# Power_Supply.net
KiCad netlist of a schematic drawn in Altium Designer
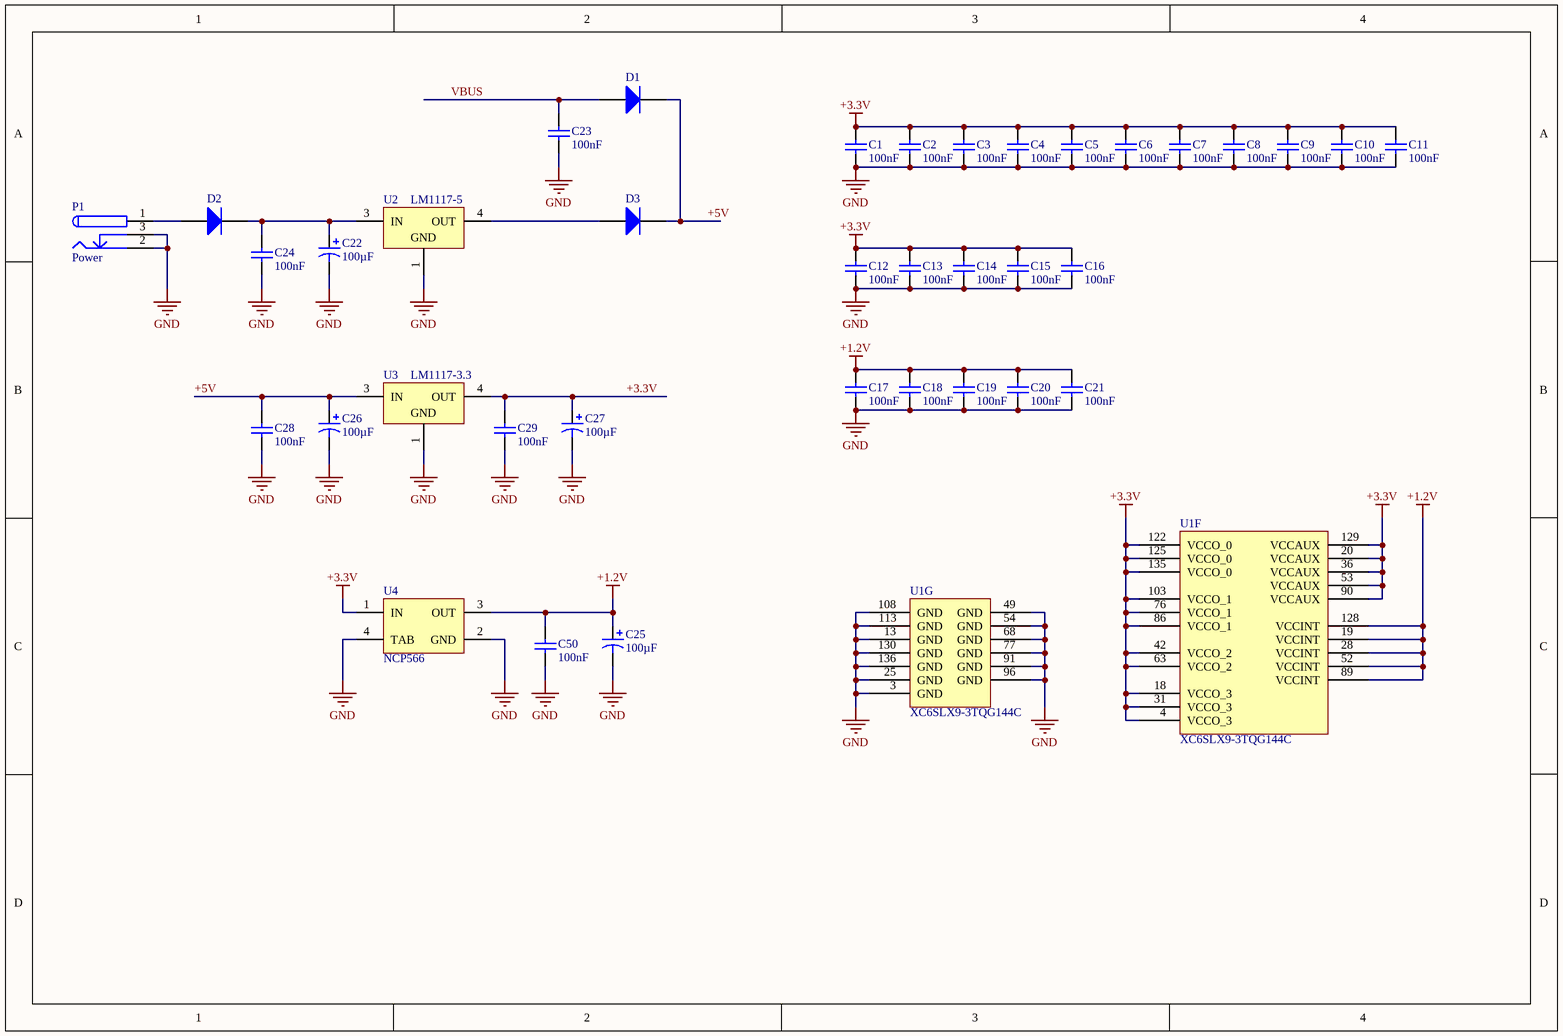
[diagram p0: Power Supply.SchDoc]

(export (version "E")
  (design (tool "Eeschema 10.0.6"))
  (components
    (comp (ref "C1")
      (value "100nF")
      (footprint "6-0805_n")
      (description "Capacitor")
      (fields (field (name "Comment") "Cap") (field (name "PUBLISHER") "Altium Limited"))
      (libsource (lib "Miscellaneous Devices") (part "Cap"))
    )
    (comp (ref "C2")
      (value "100nF")
      (footprint "6-0805_n")
      (description "Capacitor")
      (fields (field (name "Comment") "Cap") (field (name "PUBLISHER") "Altium Limited"))
      (libsource (lib "Miscellaneous Devices") (part "Cap"))
    )
    (comp (ref "C3")
      (value "100nF")
      (footprint "6-0805_n")
      (description "Capacitor")
      (fields (field (name "Comment") "Cap") (field (name "PUBLISHER") "Altium Limited"))
      (libsource (lib "Miscellaneous Devices") (part "Cap"))
    )
    (comp (ref "C4")
      (value "100nF")
      (footprint "6-0805_n")
      (description "Capacitor")
      (fields (field (name "Comment") "Cap") (field (name "PUBLISHER") "Altium Limited"))
      (libsource (lib "Miscellaneous Devices") (part "Cap"))
    )
    (comp (ref "C5")
      (value "100nF")
      (footprint "6-0805_n")
      (description "Capacitor")
      (fields (field (name "Comment") "Cap") (field (name "PUBLISHER") "Altium Limited"))
      (libsource (lib "Miscellaneous Devices") (part "Cap"))
    )
    (comp (ref "C6")
      (value "100nF")
      (footprint "6-0805_n")
      (description "Capacitor")
      (fields (field (name "Comment") "Cap") (field (name "PUBLISHER") "Altium Limited"))
      (libsource (lib "Miscellaneous Devices") (part "Cap"))
    )
    (comp (ref "C7")
      (value "100nF")
      (footprint "6-0805_n")
      (description "Capacitor")
      (fields (field (name "Comment") "Cap") (field (name "PUBLISHER") "Altium Limited"))
      (libsource (lib "Miscellaneous Devices") (part "Cap"))
    )
    (comp (ref "C8")
      (value "100nF")
      (footprint "6-0805_n")
      (description "Capacitor")
      (fields (field (name "Comment") "Cap") (field (name "PUBLISHER") "Altium Limited"))
      (libsource (lib "Miscellaneous Devices") (part "Cap"))
    )
    (comp (ref "C9")
      (value "100nF")
      (footprint "6-0805_n")
      (description "Capacitor")
      (fields (field (name "Comment") "Cap") (field (name "PUBLISHER") "Altium Limited"))
      (libsource (lib "Miscellaneous Devices") (part "Cap"))
    )
    (comp (ref "C10")
      (value "100nF")
      (footprint "6-0805_n")
      (description "Capacitor")
      (fields (field (name "Comment") "Cap") (field (name "PUBLISHER") "Altium Limited"))
      (libsource (lib "Miscellaneous Devices") (part "Cap"))
    )
    (comp (ref "C11")
      (value "100nF")
      (footprint "6-0805_n")
      (description "Capacitor")
      (fields (field (name "Comment") "Cap") (field (name "PUBLISHER") "Altium Limited"))
      (libsource (lib "Miscellaneous Devices") (part "Cap"))
    )
    (comp (ref "C12")
      (value "100nF")
      (footprint "6-0805_n")
      (description "Capacitor")
      (fields (field (name "Comment") "Cap") (field (name "PUBLISHER") "Altium Limited"))
      (libsource (lib "Miscellaneous Devices") (part "Cap"))
    )
    (comp (ref "C13")
      (value "100nF")
      (footprint "6-0805_n")
      (description "Capacitor")
      (fields (field (name "Comment") "Cap") (field (name "PUBLISHER") "Altium Limited"))
      (libsource (lib "Miscellaneous Devices") (part "Cap"))
    )
    (comp (ref "C14")
      (value "100nF")
      (footprint "6-0805_n")
      (description "Capacitor")
      (fields (field (name "Comment") "Cap") (field (name "PUBLISHER") "Altium Limited"))
      (libsource (lib "Miscellaneous Devices") (part "Cap"))
    )
    (comp (ref "C15")
      (value "100nF")
      (footprint "6-0805_n")
      (description "Capacitor")
      (fields (field (name "Comment") "Cap") (field (name "PUBLISHER") "Altium Limited"))
      (libsource (lib "Miscellaneous Devices") (part "Cap"))
    )
    (comp (ref "C16")
      (value "100nF")
      (footprint "6-0805_n")
      (description "Capacitor")
      (fields (field (name "Comment") "Cap") (field (name "PUBLISHER") "Altium Limited"))
      (libsource (lib "Miscellaneous Devices") (part "Cap"))
    )
    (comp (ref "C17")
      (value "100nF")
      (footprint "6-0805_n")
      (description "Capacitor")
      (fields (field (name "Comment") "Cap") (field (name "PUBLISHER") "Altium Limited"))
      (libsource (lib "Miscellaneous Devices") (part "Cap"))
    )
    (comp (ref "C18")
      (value "100nF")
      (footprint "6-0805_n")
      (description "Capacitor")
      (fields (field (name "Comment") "Cap") (field (name "PUBLISHER") "Altium Limited"))
      (libsource (lib "Miscellaneous Devices") (part "Cap"))
    )
    (comp (ref "C19")
      (value "100nF")
      (footprint "6-0805_n")
      (description "Capacitor")
      (fields (field (name "Comment") "Cap") (field (name "PUBLISHER") "Altium Limited"))
      (libsource (lib "Miscellaneous Devices") (part "Cap"))
    )
    (comp (ref "C20")
      (value "100nF")
      (footprint "6-0805_n")
      (description "Capacitor")
      (fields (field (name "Comment") "Cap") (field (name "PUBLISHER") "Altium Limited"))
      (libsource (lib "Miscellaneous Devices") (part "Cap"))
    )
    (comp (ref "C21")
      (value "100nF")
      (footprint "6-0805_n")
      (description "Capacitor")
      (fields (field (name "Comment") "Cap") (field (name "PUBLISHER") "Altium Limited"))
      (libsource (lib "Miscellaneous Devices") (part "Cap"))
    )
    (comp (ref "C22")
      (value "100µF")
      (footprint "ECAP 6.3mm")
      (description "Polarized Capacitor (Surface Mount)")
      (fields (field (name "Comment") "Cap Pol3") (field (name "PUBLISHER") "Altium Limited"))
      (libsource (lib "Miscellaneous Devices") (part "Cap Pol3"))
    )
    (comp (ref "C23")
      (value "100nF")
      (footprint "6-0805_n")
      (description "Capacitor")
      (fields (field (name "Comment") "Cap") (field (name "PUBLISHER") "Altium Limited"))
      (libsource (lib "Miscellaneous Devices") (part "Cap"))
    )
    (comp (ref "C24")
      (value "100nF")
      (footprint "6-0805_n")
      (description "Capacitor")
      (fields (field (name "Comment") "Cap") (field (name "PUBLISHER") "Altium Limited"))
      (libsource (lib "Miscellaneous Devices") (part "Cap"))
    )
    (comp (ref "C25")
      (value "100µF")
      (footprint "ECAP 6.3mm")
      (description "Polarized Capacitor (Surface Mount)")
      (fields (field (name "Comment") "Cap Pol3") (field (name "PUBLISHER") "Altium Limited"))
      (libsource (lib "Miscellaneous Devices") (part "Cap Pol3"))
    )
    (comp (ref "C26")
      (value "100µF")
      (footprint "ECAP 6.3mm")
      (description "Polarized Capacitor (Surface Mount)")
      (fields (field (name "Comment") "Cap Pol3") (field (name "PUBLISHER") "Altium Limited"))
      (libsource (lib "Miscellaneous Devices") (part "Cap Pol3"))
    )
    (comp (ref "C27")
      (value "100µF")
      (footprint "ECAP 6.3mm")
      (description "Polarized Capacitor (Surface Mount)")
      (fields (field (name "Comment") "Cap Pol3") (field (name "PUBLISHER") "Altium Limited"))
      (libsource (lib "Miscellaneous Devices") (part "Cap Pol3"))
    )
    (comp (ref "C28")
      (value "100nF")
      (footprint "6-0805_n")
      (description "Capacitor")
      (fields (field (name "Comment") "Cap") (field (name "PUBLISHER") "Altium Limited"))
      (libsource (lib "Miscellaneous Devices") (part "Cap"))
    )
    (comp (ref "C29")
      (value "100nF")
      (footprint "6-0805_n")
      (description "Capacitor")
      (fields (field (name "Comment") "Cap") (field (name "PUBLISHER") "Altium Limited"))
      (libsource (lib "Miscellaneous Devices") (part "Cap"))
    )
    (comp (ref "C50")
      (value "100nF")
      (footprint "6-0805_n")
      (description "Capacitor")
      (fields (field (name "Comment") "Cap") (field (name "PUBLISHER") "Altium Limited"))
      (libsource (lib "Miscellaneous Devices") (part "Cap"))
    )
    (comp (ref "D1")
      (value "Diode")
      (footprint "SMB")
      (description "Default Diode")
      (fields (field (name "PUBLISHER") "Altium Limited"))
      (libsource (lib "Miscellaneous Devices") (part "Diode"))
    )
    (comp (ref "D2")
      (value "Diode")
      (footprint "SMB")
      (description "Default Diode")
      (fields (field (name "PUBLISHER") "Altium Limited"))
      (libsource (lib "Miscellaneous Devices") (part "Diode"))
    )
    (comp (ref "D3")
      (value "Diode")
      (footprint "SMB")
      (description "Default Diode")
      (fields (field (name "PUBLISHER") "Altium Limited"))
      (libsource (lib "Miscellaneous Devices") (part "Diode"))
    )
    (comp (ref "P1")
      (value "Power")
      (footprint "Power Jack")
      (libsource (lib "Connectors") (part "Power Jack"))
    )
    (comp (ref "U1")
      (value "XC6SLX9-3TQG144C")
      (footprint "TQG144_N")
      (fields (field (name "PUBLISHER") "Altium Limited"))
      (libsource (lib "Xilinx Spartan-6") (part "XC6SLX9-3TQG144C"))
    )
    (comp (ref "U2")
      (value "LM1117-5")
      (footprint "TD03B_M")
      (description "800mA Low-Dropout Linear Regulator, 3-pin TO-252")
      (fields
        (field (name "PARTNUMBER") "LM1117DT-3.3")
        (field (name "MANUFACTURER") "National Semiconductor")
        (field (name "PUBLISHER") "Altium Limited")
      )
      (libsource (lib "NSC LDO") (part "LM1117DT-3.3"))
    )
    (comp (ref "U3")
      (value "LM1117-3.3")
      (footprint "TD03B_M")
      (description "800mA Low-Dropout Linear Regulator, 3-pin TO-252")
      (fields
        (field (name "PARTNUMBER") "LM1117DT-3.3")
        (field (name "MANUFACTURER") "National Semiconductor")
        (field (name "PUBLISHER") "Altium Limited")
      )
      (libsource (lib "NSC LDO") (part "LM1117DT-3.3"))
    )
    (comp (ref "U4") (value "NCP566") (footprint "SOT223") (libsource (lib "Semicon") (part "NCP566")))
  )
  (nets
    (net (code "1") (name "+1.2V") (class "Default")
      (node (ref "C17") (pin "2") (pinfunction "2_2") (pintype "passive"))
      (node (ref "C18") (pin "2") (pinfunction "2_2") (pintype "passive"))
      (node (ref "C19") (pin "2") (pinfunction "2_2") (pintype "passive"))
      (node (ref "C20") (pin "2") (pinfunction "2_2") (pintype "passive"))
      (node (ref "C21") (pin "2") (pinfunction "2_2") (pintype "passive"))
      (node (ref "C25") (pin "1") (pinfunction "1_1") (pintype "passive"))
      (node (ref "C50") (pin "2") (pinfunction "2_2") (pintype "passive"))
      (node (ref "U1") (pin "128") (pinfunction "VCCINT_128") (pintype "power_in"))
      (node (ref "U1") (pin "19") (pinfunction "VCCINT_19") (pintype "power_in"))
      (node (ref "U1") (pin "28") (pinfunction "VCCINT_28") (pintype "power_in"))
      (node (ref "U1") (pin "52") (pinfunction "VCCINT_52") (pintype "power_in"))
      (node (ref "U1") (pin "89") (pinfunction "VCCINT_89") (pintype "power_in"))
      (node (ref "U4") (pin "3") (pinfunction "OUT_3") (pintype "power_in"))
    )
    (net (code "2") (name "+3.3V") (class "Default")
      (node (ref "C1") (pin "2") (pinfunction "2_2") (pintype "passive"))
      (node (ref "C10") (pin "2") (pinfunction "2_2") (pintype "passive"))
      (node (ref "C11") (pin "2") (pinfunction "2_2") (pintype "passive"))
      (node (ref "C12") (pin "2") (pinfunction "2_2") (pintype "passive"))
      (node (ref "C13") (pin "2") (pinfunction "2_2") (pintype "passive"))
      (node (ref "C14") (pin "2") (pinfunction "2_2") (pintype "passive"))
      (node (ref "C15") (pin "2") (pinfunction "2_2") (pintype "passive"))
      (node (ref "C16") (pin "2") (pinfunction "2_2") (pintype "passive"))
      (node (ref "C2") (pin "2") (pinfunction "2_2") (pintype "passive"))
      (node (ref "C27") (pin "1") (pinfunction "1_1") (pintype "passive"))
      (node (ref "C29") (pin "2") (pinfunction "2_2") (pintype "passive"))
      (node (ref "C3") (pin "2") (pinfunction "2_2") (pintype "passive"))
      (node (ref "C4") (pin "2") (pinfunction "2_2") (pintype "passive"))
      (node (ref "C5") (pin "2") (pinfunction "2_2") (pintype "passive"))
      (node (ref "C6") (pin "2") (pinfunction "2_2") (pintype "passive"))
      (node (ref "C7") (pin "2") (pinfunction "2_2") (pintype "passive"))
      (node (ref "C8") (pin "2") (pinfunction "2_2") (pintype "passive"))
      (node (ref "C9") (pin "2") (pinfunction "2_2") (pintype "passive"))
      (node (ref "U1") (pin "103") (pinfunction "VCCO_1_103") (pintype "power_in"))
      (node (ref "U1") (pin "122") (pinfunction "VCCO_0_122") (pintype "power_in"))
      (node (ref "U1") (pin "125") (pinfunction "VCCO_0_125") (pintype "power_in"))
      (node (ref "U1") (pin "129") (pinfunction "VCCAUX_129") (pintype "power_in"))
      (node (ref "U1") (pin "135") (pinfunction "VCCO_0_135") (pintype "power_in"))
      (node (ref "U1") (pin "18") (pinfunction "VCCO_3_18") (pintype "power_in"))
      (node (ref "U1") (pin "20") (pinfunction "VCCAUX_20") (pintype "power_in"))
      (node (ref "U1") (pin "31") (pinfunction "VCCO_3_31") (pintype "power_in"))
      (node (ref "U1") (pin "36") (pinfunction "VCCAUX_36") (pintype "power_in"))
      (node (ref "U1") (pin "4") (pinfunction "VCCO_3_4") (pintype "power_in"))
      (node (ref "U1") (pin "42") (pinfunction "VCCO_2_42") (pintype "power_in"))
      (node (ref "U1") (pin "53") (pinfunction "VCCAUX_53") (pintype "power_in"))
      (node (ref "U1") (pin "63") (pinfunction "VCCO_2_63") (pintype "power_in"))
      (node (ref "U1") (pin "76") (pinfunction "VCCO_1_76") (pintype "power_in"))
      (node (ref "U1") (pin "86") (pinfunction "VCCO_1_86") (pintype "power_in"))
      (node (ref "U1") (pin "90") (pinfunction "VCCAUX_90") (pintype "power_in"))
      (node (ref "U3") (pin "4") (pinfunction "OUT_4") (pintype "power_in"))
      (node (ref "U4") (pin "1") (pinfunction "IN_1") (pintype "power_in"))
    )
    (net (code "3") (name "/+5V") (class "Default")
      (node (ref "C26") (pin "1") (pinfunction "1_1") (pintype "passive"))
      (node (ref "C28") (pin "2") (pinfunction "2_2") (pintype "passive"))
      (node (ref "D1") (pin "2") (pinfunction "K_2") (pintype "passive"))
      (node (ref "D3") (pin "2") (pinfunction "K_2") (pintype "passive"))
      (node (ref "U3") (pin "3") (pinfunction "IN_3") (pintype "power_in"))
    )
    (net (code "4") (name "/VBUS") (class "Default")
      (node (ref "C23") (pin "2") (pinfunction "2_2") (pintype "passive"))
      (node (ref "D1") (pin "1") (pinfunction "A_1") (pintype "passive"))
    )
    (net (code "5") (name "GND") (class "Default")
      (node (ref "C1") (pin "1") (pinfunction "1_1") (pintype "passive"))
      (node (ref "C10") (pin "1") (pinfunction "1_1") (pintype "passive"))
      (node (ref "C11") (pin "1") (pinfunction "1_1") (pintype "passive"))
      (node (ref "C12") (pin "1") (pinfunction "1_1") (pintype "passive"))
      (node (ref "C13") (pin "1") (pinfunction "1_1") (pintype "passive"))
      (node (ref "C14") (pin "1") (pinfunction "1_1") (pintype "passive"))
      (node (ref "C15") (pin "1") (pinfunction "1_1") (pintype "passive"))
      (node (ref "C16") (pin "1") (pinfunction "1_1") (pintype "passive"))
      (node (ref "C17") (pin "1") (pinfunction "1_1") (pintype "passive"))
      (node (ref "C18") (pin "1") (pinfunction "1_1") (pintype "passive"))
      (node (ref "C19") (pin "1") (pinfunction "1_1") (pintype "passive"))
      (node (ref "C2") (pin "1") (pinfunction "1_1") (pintype "passive"))
      (node (ref "C20") (pin "1") (pinfunction "1_1") (pintype "passive"))
      (node (ref "C21") (pin "1") (pinfunction "1_1") (pintype "passive"))
      (node (ref "C22") (pin "2") (pinfunction "2_2") (pintype "passive"))
      (node (ref "C23") (pin "1") (pinfunction "1_1") (pintype "passive"))
      (node (ref "C24") (pin "1") (pinfunction "1_1") (pintype "passive"))
      (node (ref "C25") (pin "2") (pinfunction "2_2") (pintype "passive"))
      (node (ref "C26") (pin "2") (pinfunction "2_2") (pintype "passive"))
      (node (ref "C27") (pin "2") (pinfunction "2_2") (pintype "passive"))
      (node (ref "C28") (pin "1") (pinfunction "1_1") (pintype "passive"))
      (node (ref "C29") (pin "1") (pinfunction "1_1") (pintype "passive"))
      (node (ref "C3") (pin "1") (pinfunction "1_1") (pintype "passive"))
      (node (ref "C4") (pin "1") (pinfunction "1_1") (pintype "passive"))
      (node (ref "C5") (pin "1") (pinfunction "1_1") (pintype "passive"))
      (node (ref "C50") (pin "1") (pinfunction "1_1") (pintype "passive"))
      (node (ref "C6") (pin "1") (pinfunction "1_1") (pintype "passive"))
      (node (ref "C7") (pin "1") (pinfunction "1_1") (pintype "passive"))
      (node (ref "C8") (pin "1") (pinfunction "1_1") (pintype "passive"))
      (node (ref "C9") (pin "1") (pinfunction "1_1") (pintype "passive"))
      (node (ref "P1") (pin "2") (pinfunction "2_2") (pintype "power_in"))
      (node (ref "P1") (pin "3") (pinfunction "3_3") (pintype "power_in"))
      (node (ref "U1") (pin "108") (pinfunction "GND_108") (pintype "power_in"))
      (node (ref "U1") (pin "113") (pinfunction "GND_113") (pintype "power_in"))
      (node (ref "U1") (pin "13") (pinfunction "GND_13") (pintype "power_in"))
      (node (ref "U1") (pin "130") (pinfunction "GND_130") (pintype "power_in"))
      (node (ref "U1") (pin "136") (pinfunction "GND_136") (pintype "power_in"))
      (node (ref "U1") (pin "25") (pinfunction "GND_25") (pintype "power_in"))
      (node (ref "U1") (pin "3") (pinfunction "GND_3") (pintype "power_in"))
      (node (ref "U1") (pin "49") (pinfunction "GND_49") (pintype "power_in"))
      (node (ref "U1") (pin "54") (pinfunction "GND_54") (pintype "power_in"))
      (node (ref "U1") (pin "68") (pinfunction "GND_68") (pintype "power_in"))
      (node (ref "U1") (pin "77") (pinfunction "GND_77") (pintype "power_in"))
      (node (ref "U1") (pin "91") (pinfunction "GND_91") (pintype "power_in"))
      (node (ref "U1") (pin "96") (pinfunction "GND_96") (pintype "power_in"))
      (node (ref "U2") (pin "1") (pinfunction "GND_1") (pintype "power_in"))
      (node (ref "U3") (pin "1") (pinfunction "GND_1") (pintype "power_in"))
      (node (ref "U4") (pin "2") (pinfunction "GND_2") (pintype "power_in"))
      (node (ref "U4") (pin "4") (pinfunction "TAB_4") (pintype "power_in"))
    )
    (net (code "6") (name "Net-(D2-A)") (class "Default")
      (node (ref "D2") (pin "1") (pinfunction "A_1") (pintype "passive"))
      (node (ref "P1") (pin "1") (pinfunction "1_1") (pintype "power_in"))
    )
    (net (code "7") (name "Net-(D2-K)") (class "Default")
      (node (ref "C22") (pin "1") (pinfunction "1_1") (pintype "passive"))
      (node (ref "C24") (pin "2") (pinfunction "2_2") (pintype "passive"))
      (node (ref "D2") (pin "2") (pinfunction "K_2") (pintype "passive"))
      (node (ref "U2") (pin "3") (pinfunction "IN_3") (pintype "power_in"))
    )
    (net (code "8") (name "Net-(D3-A)") (class "Default")
      (node (ref "D3") (pin "1") (pinfunction "A_1") (pintype "passive"))
      (node (ref "U2") (pin "4") (pinfunction "OUT_4") (pintype "power_in"))
    )
  )
)
